# shield_draft.net
KiCad netlist of a schematic drawn in EAGLE
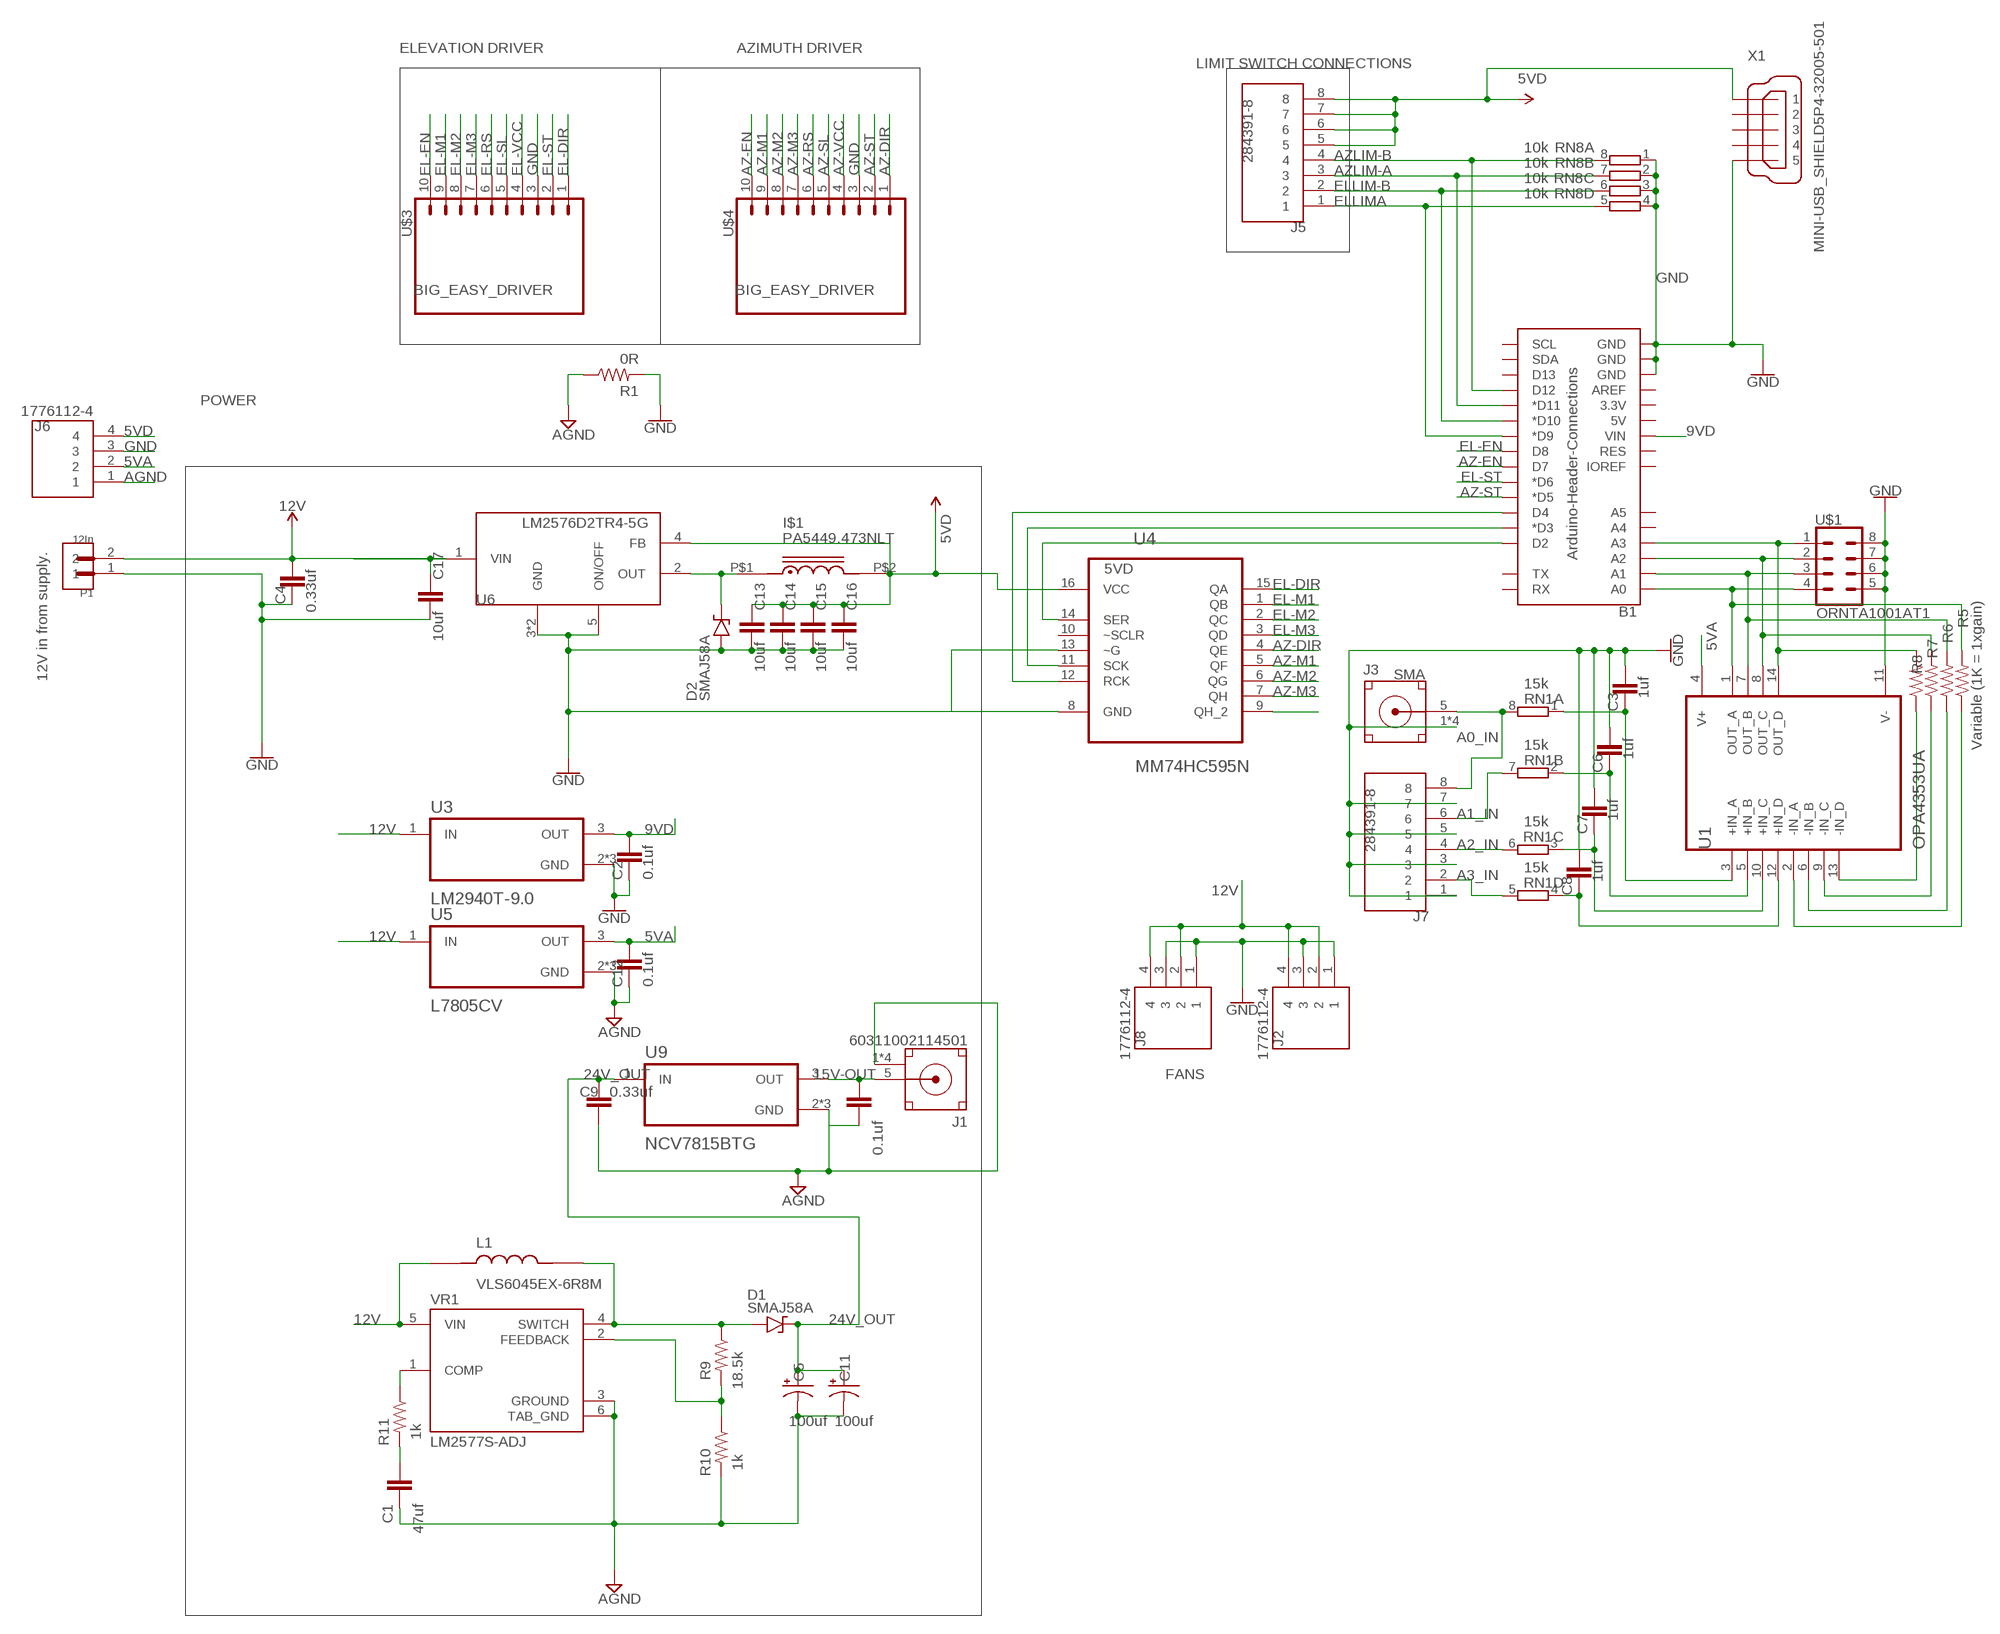
[diagram p0: schematic, sheet 1]

(export (version "E")
  (design (tool "Eeschema 10.0.6"))
  (components
    (comp (ref "B1")
      (value "Arduino-Header-Connections")
      (footprint "eagle-import:UNO_R3_SHIELD")
      (libsource (lib "eagle-import") (part "ARDUINO_UNO_R3_SHIELDBASIC"))
    )
    (comp (ref "C1")
      (value "47uf")
      (footprint "eagle-import:CAP_0805")
      (fields
        (field (name "DIGIKEY_PART_NUMBER") "311-1140-2-ND")
        (field (name "MANUFACTURER") "Yageo")
        (field (name "MPN") "CC0805KRX7R9BB104")
        (field (name "CREATED_BY") "PCBLayout.com")
      )
      (libsource (lib "eagle-import") (part "CC0805KRX7R9BB104"))
    )
    (comp (ref "C2")
      (value "0.1uf")
      (footprint "eagle-import:CAP_0805")
      (fields
        (field (name "DIGIKEY_PART_NUMBER") "311-1140-2-ND")
        (field (name "MANUFACTURER") "Yageo")
        (field (name "MPN") "CC0805KRX7R9BB104")
        (field (name "CREATED_BY") "PCBLayout.com")
      )
      (libsource (lib "eagle-import") (part "CC0805KRX7R9BB104"))
    )
    (comp (ref "C3")
      (value "1uf")
      (footprint "eagle-import:CAP_0805")
      (fields
        (field (name "DIGIKEY_PART_NUMBER") "311-1140-2-ND")
        (field (name "MANUFACTURER") "Yageo")
        (field (name "MPN") "CC0805KRX7R9BB104")
        (field (name "CREATED_BY") "PCBLayout.com")
      )
      (libsource (lib "eagle-import") (part "CC0805KRX7R9BB104"))
    )
    (comp (ref "C4")
      (value "0.33uf")
      (footprint "eagle-import:CAP_0805")
      (fields
        (field (name "DIGIKEY_PART_NUMBER") "311-1140-2-ND")
        (field (name "MANUFACTURER") "Yageo")
        (field (name "MPN") "CC0805KRX7R9BB104")
        (field (name "CREATED_BY") "PCBLayout.com")
      )
      (libsource (lib "eagle-import") (part "CC0805KRX7R9BB104"))
    )
    (comp (ref "C5")
      (value "100uf")
      (footprint "eagle-import:E5-10,5")
      (libsource (lib "eagle-import") (part "CAPACITOR-PE5-10.5"))
    )
    (comp (ref "C6")
      (value "1uf")
      (footprint "eagle-import:CAP_0805")
      (fields
        (field (name "DIGIKEY_PART_NUMBER") "311-1140-2-ND")
        (field (name "MANUFACTURER") "Yageo")
        (field (name "MPN") "CC0805KRX7R9BB104")
        (field (name "CREATED_BY") "PCBLayout.com")
      )
      (libsource (lib "eagle-import") (part "CC0805KRX7R9BB104"))
    )
    (comp (ref "C7")
      (value "1uf")
      (footprint "eagle-import:CAP_0805")
      (fields
        (field (name "DIGIKEY_PART_NUMBER") "311-1140-2-ND")
        (field (name "MANUFACTURER") "Yageo")
        (field (name "MPN") "CC0805KRX7R9BB104")
        (field (name "CREATED_BY") "PCBLayout.com")
      )
      (libsource (lib "eagle-import") (part "CC0805KRX7R9BB104"))
    )
    (comp (ref "C8")
      (value "1uf")
      (footprint "eagle-import:CAP_0805")
      (fields
        (field (name "DIGIKEY_PART_NUMBER") "311-1140-2-ND")
        (field (name "MANUFACTURER") "Yageo")
        (field (name "MPN") "CC0805KRX7R9BB104")
        (field (name "CREATED_BY") "PCBLayout.com")
      )
      (libsource (lib "eagle-import") (part "CC0805KRX7R9BB104"))
    )
    (comp (ref "C9")
      (value "0.33uf")
      (footprint "eagle-import:CAP_0805")
      (fields
        (field (name "DIGIKEY_PART_NUMBER") "311-1140-2-ND")
        (field (name "MANUFACTURER") "Yageo")
        (field (name "MPN") "CC0805KRX7R9BB104")
        (field (name "CREATED_BY") "PCBLayout.com")
      )
      (libsource (lib "eagle-import") (part "CC0805KRX7R9BB104"))
    )
    (comp (ref "C10")
      (value "0.1uf")
      (footprint "eagle-import:CAP_0805")
      (fields
        (field (name "DIGIKEY_PART_NUMBER") "311-1140-2-ND")
        (field (name "MANUFACTURER") "Yageo")
        (field (name "MPN") "CC0805KRX7R9BB104")
        (field (name "CREATED_BY") "PCBLayout.com")
      )
      (libsource (lib "eagle-import") (part "CC0805KRX7R9BB104"))
    )
    (comp (ref "C11")
      (value "100uf")
      (footprint "eagle-import:E5-10,5")
      (libsource (lib "eagle-import") (part "CAPACITOR-PE5-10.5"))
    )
    (comp (ref "C12")
      (value "0.1uf")
      (footprint "eagle-import:CAP_0805")
      (fields
        (field (name "DIGIKEY_PART_NUMBER") "311-1140-2-ND")
        (field (name "MANUFACTURER") "Yageo")
        (field (name "MPN") "CC0805KRX7R9BB104")
        (field (name "CREATED_BY") "PCBLayout.com")
      )
      (libsource (lib "eagle-import") (part "CC0805KRX7R9BB104"))
    )
    (comp (ref "C13")
      (value "10uf")
      (footprint "eagle-import:0805")
      (libsource (lib "eagle-import") (part "39NF-0805-50V-10%"))
    )
    (comp (ref "C14")
      (value "10uf")
      (footprint "eagle-import:0805")
      (libsource (lib "eagle-import") (part "39NF-0805-50V-10%"))
    )
    (comp (ref "C15")
      (value "10uf")
      (footprint "eagle-import:0805")
      (libsource (lib "eagle-import") (part "39NF-0805-50V-10%"))
    )
    (comp (ref "C16")
      (value "10uf")
      (footprint "eagle-import:0805")
      (libsource (lib "eagle-import") (part "39NF-0805-50V-10%"))
    )
    (comp (ref "C17")
      (value "10uf")
      (footprint "eagle-import:0805")
      (libsource (lib "eagle-import") (part "39NF-0805-50V-10%"))
    )
    (comp (ref "D1")
      (value "SMAJ58A")
      (footprint "eagle-import:SMA")
      (fields (field (name "MF") "Littelfuse Inc."))
      (libsource (lib "eagle-import") (part "SMAJ58A"))
    )
    (comp (ref "D2")
      (value "SMAJ58A")
      (footprint "eagle-import:SMA")
      (fields (field (name "MF") "Littelfuse Inc."))
      (libsource (lib "eagle-import") (part "SMAJ58A"))
    )
    (comp (ref "I$1")
      (value "PA5449.473NLT")
      (footprint "eagle-import:IND_TYS4020470M-10")
      (libsource (lib "eagle-import") (part "PULSE_ELECTRONICS_INDUCTOR"))
    )
    (comp (ref "J1")
      (value "60311002114501")
      (footprint "eagle-import:60311002114501")
      (fields
        (field (name "DIGIKEY_PART_NUMBER") "732-13833-ND")
        (field (name "MANUFACTURER") "Wurth Electronics Inc.")
        (field (name "CREATED_BY") "PCBLayout.com")
      )
      (libsource (lib "eagle-import") (part "60311002114501"))
    )
    (comp (ref "J2")
      (value "1776112-4")
      (footprint "eagle-import:TE_1776112-4")
      (fields (field (name "MF") "TE Connectivity"))
      (libsource (lib "eagle-import") (part "1776112-4"))
    )
    (comp (ref "J3")
      (value "SMA")
      (footprint "eagle-import:60311002114501")
      (fields
        (field (name "DIGIKEY_PART_NUMBER") "732-13833-ND")
        (field (name "MANUFACTURER") "Wurth Electronics Inc.")
        (field (name "MPN") "60311002114501")
        (field (name "CREATED_BY") "PCBLayout.com")
      )
      (libsource (lib "eagle-import") (part "60311002114501"))
    )
    (comp (ref "J5")
      (value "284391-8")
      (footprint "eagle-import:TE_284391-8")
      (fields (field (name "MF") "TE Connectivity"))
      (libsource (lib "eagle-import") (part "284391-8"))
    )
    (comp (ref "J6")
      (value "1776112-4")
      (footprint "eagle-import:TE_1776112-4")
      (fields (field (name "MF") "TE Connectivity"))
      (libsource (lib "eagle-import") (part "1776112-4"))
    )
    (comp (ref "J7")
      (value "284391-8")
      (footprint "eagle-import:TE_284391-8")
      (fields (field (name "MF") "TE Connectivity"))
      (libsource (lib "eagle-import") (part "284391-8"))
    )
    (comp (ref "J8")
      (value "1776112-4")
      (footprint "eagle-import:TE_1776112-4")
      (fields (field (name "MF") "TE Connectivity"))
      (libsource (lib "eagle-import") (part "1776112-4"))
    )
    (comp (ref "L1")
      (value "VLS6045EX-6R8M")
      (footprint "eagle-import:IND_VLS6045EX-6R8M")
      (fields (field (name "MF") "TDK") (field (name "MP") "VLS6045EX6R8M"))
      (libsource (lib "eagle-import") (part "VLS6045EX-6R8M"))
    )
    (comp (ref "P1")
      (value "12In")
      (footprint "eagle-import:OST_OSTTE020104")
      (fields (field (name "MF") "On Shore") (field (name "MP") "OSTTE020104"))
      (libsource (lib "eagle-import") (part "OSTTE020104"))
    )
    (comp (ref "R1")
      (value "0R")
      (footprint "eagle-import:0603")
      (libsource (lib "eagle-import") (part "1OHM-0603-1/10W-1%"))
    )
    (comp (ref "R5")
      (value "Variable (1K = 1xgain)")
      (footprint "eagle-import:RESAD1176W63L850D250B")
      (libsource (lib "eagle-import") (part "R-USAXIAL-11.7MM-PITCH_"))
    )
    (comp (ref "R6")
      (value "Var")
      (footprint "eagle-import:RESAD1176W63L850D250B")
      (libsource (lib "eagle-import") (part "R-USAXIAL-11.7MM-PITCH_"))
    )
    (comp (ref "R7")
      (value "Var")
      (footprint "eagle-import:RESAD1176W63L850D250B")
      (libsource (lib "eagle-import") (part "R-USAXIAL-11.7MM-PITCH_"))
    )
    (comp (ref "R8")
      (value "Var")
      (footprint "eagle-import:RESAD1176W63L850D250B")
      (libsource (lib "eagle-import") (part "R-USAXIAL-11.7MM-PITCH_"))
    )
    (comp (ref "R9")
      (value "18.5k")
      (footprint "eagle-import:0603")
      (libsource (lib "eagle-import") (part "1OHM-0603-1/10W-1%"))
    )
    (comp (ref "R10")
      (value "1k")
      (footprint "eagle-import:0603")
      (libsource (lib "eagle-import") (part "1OHM-0603-1/10W-1%"))
    )
    (comp (ref "R11")
      (value "1k")
      (footprint "eagle-import:0603")
      (libsource (lib "eagle-import") (part "1OHM-0603-1/10W-1%"))
    )
    (comp (ref "RN1")
      (value "15k")
      (footprint "eagle-import:CAY16")
      (fields (field (name "PART_NUMBER") "064R_10K_/_CAY16-103J4LF"))
      (libsource (lib "eagle-import") (part "0016_064R_10K_/_CAY16-103J4LF"))
    )
    (comp (ref "RN8")
      (value "10k")
      (footprint "eagle-import:CAY16")
      (fields (field (name "PART_NUMBER") "064R_10K_/_CAY16-103J4LF"))
      (libsource (lib "eagle-import") (part "0016_064R_10K_/_CAY16-103J4LF"))
    )
    (comp (ref "U$1")
      (value "ORNTA1001AT1")
      (footprint "eagle-import:SOIC127P600X175-8N")
      (libsource (lib "eagle-import") (part "ORNTA1001AT1"))
    )
    (comp (ref "U$3")
      (value "BIG_EASY_DRIVER")
      (footprint "eagle-import:EASY_DRIVER_FTPRT")
      (libsource (lib "eagle-import") (part "BIG_EASY_DRIVER"))
    )
    (comp (ref "U$4")
      (value "BIG_EASY_DRIVER")
      (footprint "eagle-import:EASY_DRIVER_FTPRT")
      (libsource (lib "eagle-import") (part "BIG_EASY_DRIVER"))
    )
    (comp (ref "U1")
      (value "OPA4353UA")
      (footprint "eagle-import:SOIC127P600X175-14N")
      (fields (field (name "MF") "Texas Instruments"))
      (libsource (lib "eagle-import") (part "OPA4353UA"))
    )
    (comp (ref "U3")
      (value "LM2940T-9.0")
      (footprint "eagle-import:TO254P1054X470X1955-3")
      (fields (field (name "MF") "Texas Instruments") (field (name "MP") "LM2940T-9.0/NOPB"))
      (libsource (lib "eagle-import") (part "LM2940T-9.0"))
    )
    (comp (ref "U4")
      (value "MM74HC595N")
      (footprint "eagle-import:DIP254P762X533-16")
      (fields (field (name "MF") "ON Semiconductor"))
      (libsource (lib "eagle-import") (part "MM74HC595N"))
    )
    (comp (ref "U5")
      (value "L7805CV")
      (footprint "eagle-import:TO254P1054X470X1955-3")
      (fields (field (name "MF") "Texas Instruments") (field (name "MP") "LM2940T-9.0/NOPB"))
      (libsource (lib "eagle-import") (part "LM2940T-9.0"))
    )
    (comp (ref "U6")
      (value "LM2576D2TR4-5G")
      (footprint "eagle-import:D2PAK-5")
      (fields (field (name "MF") "ON Semiconductor"))
      (libsource (lib "eagle-import") (part "LM2576D2TR4-5G"))
    )
    (comp (ref "U9")
      (value "NCV7815BTG")
      (footprint "eagle-import:TO254P1054X470X1955-3")
      (fields (field (name "MF") "Texas Instruments") (field (name "MP") "LM2940T-9.0/NOPB"))
      (libsource (lib "eagle-import") (part "LM2940T-9.0"))
    )
    (comp (ref "VR1")
      (value "LM2577S-ADJ")
      (footprint "eagle-import:TO170P1524X483-6N")
      (fields (field (name "MF") "Texas Instruments"))
      (libsource (lib "eagle-import") (part "LM2577S-ADJ"))
    )
    (comp (ref "X1")
      (value "MINI-USB_SHIELD5P4-32005-501")
      (footprint "eagle-import:32005-501")
      (libsource (lib "eagle-import") (part "MINI-USB_SHIELD5P4-32005-501"))
    )
  )
  (nets
    (net (code "1") (name "/5VA") (class "Default")
      (node (ref "C12") (pin "2") (pinfunction "2_2") (pintype "passive"))
      (node (ref "J6") (pin "2") (pinfunction "2_2") (pintype "passive"))
      (node (ref "U1") (pin "4") (pinfunction "V+_4") (pintype "power_in"))
      (node (ref "U5") (pin "3") (pinfunction "OUT_3") (pintype "output"))
    )
    (net (code "2") (name "/9VD") (class "Default")
      (node (ref "B1") (pin "VIN") (pinfunction "VIN_VIN") (pintype "bidirectional"))
      (node (ref "C2") (pin "2") (pinfunction "2_2") (pintype "passive"))
      (node (ref "U3") (pin "3") (pinfunction "OUT_3") (pintype "output"))
    )
    (net (code "3") (name "/15V-OUT") (class "Default")
      (node (ref "C10") (pin "2") (pinfunction "2_2") (pintype "passive"))
      (node (ref "J1") (pin "5") (pinfunction "SIGNAL_5") (pintype "passive"))
      (node (ref "U9") (pin "3") (pinfunction "OUT_3") (pintype "output"))
    )
    (net (code "4") (name "/24V_OUT") (class "Default")
      (node (ref "C11") (pin "+") (pinfunction "+_+") (pintype "passive"))
      (node (ref "C5") (pin "+") (pinfunction "+_+") (pintype "passive"))
      (node (ref "C9") (pin "2") (pinfunction "2_2") (pintype "passive"))
      (node (ref "D1") (pin "C") (pinfunction "C_C") (pintype "passive"))
      (node (ref "U9") (pin "1") (pinfunction "IN_1") (pintype "input"))
    )
    (net (code "5") (name "/A0_IN") (class "Default")
      (node (ref "J3") (pin "5") (pinfunction "SIGNAL_5") (pintype "passive"))
      (node (ref "J7") (pin "8") (pinfunction "8_8") (pintype "passive"))
      (node (ref "RN1") (pin "8") (pinfunction "2_8") (pintype "passive"))
    )
    (net (code "6") (name "/A1_IN") (class "Default")
      (node (ref "J7") (pin "6") (pinfunction "6_6") (pintype "passive"))
      (node (ref "RN1") (pin "7") (pinfunction "2_7") (pintype "passive"))
    )
    (net (code "7") (name "/A2_IN") (class "Default")
      (node (ref "J7") (pin "4") (pinfunction "4_4") (pintype "passive"))
      (node (ref "RN1") (pin "6") (pinfunction "2_6") (pintype "passive"))
    )
    (net (code "8") (name "/A3_IN") (class "Default")
      (node (ref "J7") (pin "2") (pinfunction "2_2") (pintype "passive"))
      (node (ref "RN1") (pin "5") (pinfunction "2_5") (pintype "passive"))
    )
    (net (code "9") (name "/AZ-DIR") (class "Default")
      (node (ref "U$4") (pin "1") (pinfunction "1_1") (pintype "passive"))
      (node (ref "U4") (pin "4") (pinfunction "QE_4") (pintype "output"))
    )
    (net (code "10") (name "/AZ-EN") (class "Default")
      (node (ref "B1") (pin "D7") (pinfunction "D7_D7") (pintype "bidirectional"))
      (node (ref "U$4") (pin "10") (pinfunction "10_10") (pintype "passive"))
    )
    (net (code "11") (name "/AZ-M1") (class "Default")
      (node (ref "U$4") (pin "9") (pinfunction "9_9") (pintype "passive"))
      (node (ref "U4") (pin "5") (pinfunction "QF_5") (pintype "output"))
    )
    (net (code "12") (name "/AZ-M2") (class "Default")
      (node (ref "U$4") (pin "8") (pinfunction "8_8") (pintype "passive"))
      (node (ref "U4") (pin "6") (pinfunction "QG_6") (pintype "output"))
    )
    (net (code "13") (name "/AZ-M3") (class "Default")
      (node (ref "U$4") (pin "7") (pinfunction "7_7") (pintype "passive"))
      (node (ref "U4") (pin "7") (pinfunction "QH_7") (pintype "output"))
    )
    (net (code "14") (name "/AZ-RS") (class "Default")
      (node (ref "U$4") (pin "6") (pinfunction "6_6") (pintype "passive"))
    )
    (net (code "15") (name "/AZ-SL") (class "Default")
      (node (ref "U$4") (pin "5") (pinfunction "5_5") (pintype "passive"))
    )
    (net (code "16") (name "/AZ-ST") (class "Default")
      (node (ref "B1") (pin "D5") (pinfunction "*D5_D5") (pintype "bidirectional"))
      (node (ref "U$4") (pin "2") (pinfunction "2_2") (pintype "passive"))
    )
    (net (code "17") (name "/AZ-VCC") (class "Default")
      (node (ref "U$4") (pin "4") (pinfunction "4_4") (pintype "passive"))
    )
    (net (code "18") (name "/AZLIM-A") (class "Default")
      (node (ref "B1") (pin "D11") (pinfunction "*D11_D11") (pintype "bidirectional"))
      (node (ref "J5") (pin "3") (pinfunction "3_3") (pintype "passive"))
      (node (ref "RN8") (pin "7") (pinfunction "2_7") (pintype "passive"))
    )
    (net (code "19") (name "/AZLIM-B") (class "Default")
      (node (ref "B1") (pin "D12") (pinfunction "D12_D12") (pintype "bidirectional"))
      (node (ref "J5") (pin "4") (pinfunction "4_4") (pintype "passive"))
      (node (ref "RN8") (pin "8") (pinfunction "2_8") (pintype "passive"))
    )
    (net (code "20") (name "/EL-DIR") (class "Default")
      (node (ref "U$3") (pin "1") (pinfunction "1_1") (pintype "passive"))
      (node (ref "U4") (pin "15") (pinfunction "QA_15") (pintype "output"))
    )
    (net (code "21") (name "/EL-EN") (class "Default")
      (node (ref "B1") (pin "D8") (pinfunction "D8_D8") (pintype "bidirectional"))
      (node (ref "U$3") (pin "10") (pinfunction "10_10") (pintype "passive"))
    )
    (net (code "22") (name "/EL-M1") (class "Default")
      (node (ref "U$3") (pin "9") (pinfunction "9_9") (pintype "passive"))
      (node (ref "U4") (pin "1") (pinfunction "QB_1") (pintype "output"))
    )
    (net (code "23") (name "/EL-M2") (class "Default")
      (node (ref "U$3") (pin "8") (pinfunction "8_8") (pintype "passive"))
      (node (ref "U4") (pin "2") (pinfunction "QC_2") (pintype "output"))
    )
    (net (code "24") (name "/EL-M3") (class "Default")
      (node (ref "U$3") (pin "7") (pinfunction "7_7") (pintype "passive"))
      (node (ref "U4") (pin "3") (pinfunction "QD_3") (pintype "output"))
    )
    (net (code "25") (name "/EL-RS") (class "Default")
      (node (ref "U$3") (pin "6") (pinfunction "6_6") (pintype "passive"))
    )
    (net (code "26") (name "/EL-SL") (class "Default")
      (node (ref "U$3") (pin "5") (pinfunction "5_5") (pintype "passive"))
    )
    (net (code "27") (name "/EL-ST") (class "Default")
      (node (ref "B1") (pin "D6") (pinfunction "*D6_D6") (pintype "bidirectional"))
      (node (ref "U$3") (pin "2") (pinfunction "2_2") (pintype "passive"))
    )
    (net (code "28") (name "/EL-VCC") (class "Default")
      (node (ref "U$3") (pin "4") (pinfunction "4_4") (pintype "passive"))
    )
    (net (code "29") (name "/ELLIM-B") (class "Default")
      (node (ref "B1") (pin "D10") (pinfunction "*D10_D10") (pintype "bidirectional"))
      (node (ref "J5") (pin "2") (pinfunction "2_2") (pintype "passive"))
      (node (ref "RN8") (pin "6") (pinfunction "2_6") (pintype "passive"))
    )
    (net (code "30") (name "/ELLIMA") (class "Default")
      (node (ref "B1") (pin "D9") (pinfunction "*D9_D9") (pintype "bidirectional"))
      (node (ref "J5") (pin "1") (pinfunction "1_1") (pintype "passive"))
      (node (ref "RN8") (pin "5") (pinfunction "2_5") (pintype "passive"))
    )
    (net (code "31") (name "5V") (class "Default")
      (node (ref "C13") (pin "1") (pinfunction "1_1") (pintype "passive"))
      (node (ref "C14") (pin "1") (pinfunction "1_1") (pintype "passive"))
      (node (ref "C15") (pin "1") (pinfunction "1_1") (pintype "passive"))
      (node (ref "C16") (pin "1") (pinfunction "1_1") (pintype "passive"))
      (node (ref "I$1") (pin "P$2") (pinfunction "2_P$2") (pintype "passive"))
      (node (ref "J5") (pin "5") (pinfunction "5_5") (pintype "passive"))
      (node (ref "J5") (pin "6") (pinfunction "6_6") (pintype "passive"))
      (node (ref "J5") (pin "7") (pinfunction "7_7") (pintype "passive"))
      (node (ref "J5") (pin "8") (pinfunction "8_8") (pintype "passive"))
      (node (ref "J6") (pin "4") (pinfunction "4_4") (pintype "passive"))
      (node (ref "U4") (pin "16") (pinfunction "VCC_16") (pintype "power_in"))
      (node (ref "U6") (pin "4") (pinfunction "FB_4") (pintype "output"))
      (node (ref "X1") (pin "1") (pinfunction "1_1") (pintype "passive"))
    )
    (net (code "32") (name "12V") (class "Default")
      (node (ref "C17") (pin "1") (pinfunction "1_1") (pintype "passive"))
      (node (ref "C4") (pin "2") (pinfunction "2_2") (pintype "passive"))
      (node (ref "J2") (pin "2") (pinfunction "2_2") (pintype "passive"))
      (node (ref "J2") (pin "4") (pinfunction "4_4") (pintype "passive"))
      (node (ref "J8") (pin "2") (pinfunction "2_2") (pintype "passive"))
      (node (ref "J8") (pin "4") (pinfunction "4_4") (pintype "passive"))
      (node (ref "L1") (pin "1") (pinfunction "1_1") (pintype "passive"))
      (node (ref "P1") (pin "2") (pinfunction "2_2") (pintype "passive"))
      (node (ref "U3") (pin "1") (pinfunction "IN_1") (pintype "input"))
      (node (ref "U5") (pin "1") (pinfunction "IN_1") (pintype "input"))
      (node (ref "U6") (pin "1") (pinfunction "VIN_1") (pintype "input"))
      (node (ref "VR1") (pin "5") (pinfunction "VIN_5") (pintype "input"))
    )
    (net (code "33") (name "AGND") (class "Default")
      (node (ref "C1") (pin "1") (pinfunction "1_1") (pintype "passive"))
      (node (ref "C10") (pin "1") (pinfunction "1_1") (pintype "passive"))
      (node (ref "C11") (pin "-") (pinfunction "-_-") (pintype "passive"))
      (node (ref "C12") (pin "1") (pinfunction "1_1") (pintype "passive"))
      (node (ref "C5") (pin "-") (pinfunction "-_-") (pintype "passive"))
      (node (ref "C9") (pin "1") (pinfunction "1_1") (pintype "passive"))
      (node (ref "J1") (pin "1") (pinfunction "GND_1") (pintype "power_in"))
      (node (ref "J1") (pin "2") (pinfunction "GND_2") (pintype "power_in"))
      (node (ref "J1") (pin "3") (pinfunction "GND_3") (pintype "power_in"))
      (node (ref "J1") (pin "4") (pinfunction "GND_4") (pintype "power_in"))
      (node (ref "J6") (pin "1") (pinfunction "1_1") (pintype "passive"))
      (node (ref "R1") (pin "1") (pinfunction "1_1") (pintype "passive"))
      (node (ref "R10") (pin "2") (pinfunction "2_2") (pintype "passive"))
      (node (ref "U5") (pin "2") (pinfunction "GND_2") (pintype "power_in"))
      (node (ref "U5") (pin "P$1") (pinfunction "GND_P$1") (pintype "power_in"))
      (node (ref "U5") (pin "P$2") (pinfunction "GND_P$2") (pintype "power_in"))
      (node (ref "U9") (pin "2") (pinfunction "GND_2") (pintype "power_in"))
      (node (ref "U9") (pin "P$1") (pinfunction "GND_P$1") (pintype "power_in"))
      (node (ref "U9") (pin "P$2") (pinfunction "GND_P$2") (pintype "power_in"))
      (node (ref "VR1") (pin "3") (pinfunction "GROUND_3") (pintype "power_in"))
      (node (ref "VR1") (pin "6") (pinfunction "TAB_GND_6") (pintype "power_in"))
    )
    (net (code "34") (name "GND") (class "Default")
      (node (ref "B1") (pin "GND@0") (pinfunction "GND_GND@0") (pintype "bidirectional"))
      (node (ref "B1") (pin "GND@1") (pinfunction "GND_GND@1") (pintype "bidirectional"))
      (node (ref "B1") (pin "GND@2") (pinfunction "GND_GND@2") (pintype "bidirectional"))
      (node (ref "C13") (pin "2") (pinfunction "2_2") (pintype "passive"))
      (node (ref "C14") (pin "2") (pinfunction "2_2") (pintype "passive"))
      (node (ref "C15") (pin "2") (pinfunction "2_2") (pintype "passive"))
      (node (ref "C16") (pin "2") (pinfunction "2_2") (pintype "passive"))
      (node (ref "C17") (pin "2") (pinfunction "2_2") (pintype "passive"))
      (node (ref "C2") (pin "1") (pinfunction "1_1") (pintype "passive"))
      (node (ref "C3") (pin "2") (pinfunction "2_2") (pintype "passive"))
      (node (ref "C4") (pin "1") (pinfunction "1_1") (pintype "passive"))
      (node (ref "C6") (pin "2") (pinfunction "2_2") (pintype "passive"))
      (node (ref "C7") (pin "2") (pinfunction "2_2") (pintype "passive"))
      (node (ref "C8") (pin "2") (pinfunction "2_2") (pintype "passive"))
      (node (ref "D2") (pin "A") (pinfunction "A_A") (pintype "passive"))
      (node (ref "J2") (pin "1") (pinfunction "1_1") (pintype "passive"))
      (node (ref "J2") (pin "3") (pinfunction "3_3") (pintype "passive"))
      (node (ref "J3") (pin "1") (pinfunction "GND_1") (pintype "power_in"))
      (node (ref "J3") (pin "2") (pinfunction "GND_2") (pintype "power_in"))
      (node (ref "J3") (pin "3") (pinfunction "GND_3") (pintype "power_in"))
      (node (ref "J3") (pin "4") (pinfunction "GND_4") (pintype "power_in"))
      (node (ref "J6") (pin "3") (pinfunction "3_3") (pintype "passive"))
      (node (ref "J7") (pin "1") (pinfunction "1_1") (pintype "passive"))
      (node (ref "J7") (pin "3") (pinfunction "3_3") (pintype "passive"))
      (node (ref "J7") (pin "5") (pinfunction "5_5") (pintype "passive"))
      (node (ref "J7") (pin "7") (pinfunction "7_7") (pintype "passive"))
      (node (ref "J8") (pin "1") (pinfunction "1_1") (pintype "passive"))
      (node (ref "J8") (pin "3") (pinfunction "3_3") (pintype "passive"))
      (node (ref "P1") (pin "1") (pinfunction "1_1") (pintype "passive"))
      (node (ref "R1") (pin "2") (pinfunction "2_2") (pintype "passive"))
      (node (ref "RN8") (pin "1") (pinfunction "1_1") (pintype "passive"))
      (node (ref "RN8") (pin "2") (pinfunction "1_2") (pintype "passive"))
      (node (ref "RN8") (pin "3") (pinfunction "1_3") (pintype "passive"))
      (node (ref "RN8") (pin "4") (pinfunction "1_4") (pintype "passive"))
      (node (ref "U$1") (pin "5") (pinfunction "R4B_5") (pintype "passive"))
      (node (ref "U$1") (pin "6") (pinfunction "R3B_6") (pintype "passive"))
      (node (ref "U$1") (pin "7") (pinfunction "R2B_7") (pintype "passive"))
      (node (ref "U$1") (pin "8") (pinfunction "R1B_8") (pintype "passive"))
      (node (ref "U$3") (pin "3") (pinfunction "3_3") (pintype "passive"))
      (node (ref "U$4") (pin "3") (pinfunction "3_3") (pintype "passive"))
      (node (ref "U1") (pin "11") (pinfunction "V-_11") (pintype "power_in"))
      (node (ref "U3") (pin "2") (pinfunction "GND_2") (pintype "power_in"))
      (node (ref "U3") (pin "P$1") (pinfunction "GND_P$1") (pintype "power_in"))
      (node (ref "U3") (pin "P$2") (pinfunction "GND_P$2") (pintype "power_in"))
      (node (ref "U4") (pin "13") (pinfunction "~{G}_13") (pintype "input"))
      (node (ref "U4") (pin "8") (pinfunction "GND_8") (pintype "passive"))
      (node (ref "U6") (pin "3") (pinfunction "GND_3") (pintype "passive"))
      (node (ref "U6") (pin "5") (pinfunction "ON/OFF_5") (pintype "input"))
      (node (ref "U6") (pin "6") (pinfunction "GND_6") (pintype "passive"))
      (node (ref "X1") (pin "5") (pinfunction "5_5") (pintype "passive"))
    )
    (net (code "35") (name "Net-(B1-*D3)") (class "Default")
      (node (ref "B1") (pin "D3") (pinfunction "*D3_D3") (pintype "bidirectional"))
      (node (ref "U4") (pin "11") (pinfunction "SCK_11") (pintype "input"))
    )
    (net (code "36") (name "Net-(C1-Pad2)") (class "Default")
      (node (ref "C1") (pin "2") (pinfunction "2_2") (pintype "passive"))
      (node (ref "R11") (pin "2") (pinfunction "2_2") (pintype "passive"))
    )
    (net (code "37") (name "Net-(I$1-1)") (class "Default")
      (node (ref "D2") (pin "C") (pinfunction "C_C") (pintype "passive"))
      (node (ref "I$1") (pin "P$1") (pinfunction "1_P$1") (pintype "passive"))
      (node (ref "U6") (pin "2") (pinfunction "OUT_2") (pintype "output"))
    )
    (net (code "38") (name "Net-(RN1B-1)") (class "Default")
      (node (ref "C6") (pin "1") (pinfunction "1_1") (pintype "passive"))
      (node (ref "RN1") (pin "2") (pinfunction "1_2") (pintype "passive"))
      (node (ref "U1") (pin "5") (pinfunction "+IN_B_5") (pintype "input"))
    )
    (net (code "39") (name "Net-(RN1C-1)") (class "Default")
      (node (ref "C7") (pin "1") (pinfunction "1_1") (pintype "passive"))
      (node (ref "RN1") (pin "3") (pinfunction "1_3") (pintype "passive"))
      (node (ref "U1") (pin "10") (pinfunction "+IN_C_10") (pintype "input"))
    )
    (net (code "40") (name "Net-(RN1D-1)") (class "Default")
      (node (ref "C8") (pin "1") (pinfunction "1_1") (pintype "passive"))
      (node (ref "RN1") (pin "4") (pinfunction "1_4") (pintype "passive"))
      (node (ref "U1") (pin "12") (pinfunction "+IN_D_12") (pintype "input"))
    )
    (net (code "41") (name "Net-(U$1-R1A)") (class "Default")
      (node (ref "B1") (pin "A3") (pinfunction "A3_A3") (pintype "bidirectional"))
      (node (ref "R8") (pin "2") (pinfunction "2_2") (pintype "passive"))
      (node (ref "U$1") (pin "1") (pinfunction "R1A_1") (pintype "passive"))
      (node (ref "U1") (pin "14") (pinfunction "OUT_D_14") (pintype "output"))
    )
    (net (code "42") (name "Net-(U$1-R2A)") (class "Default")
      (node (ref "B1") (pin "A2") (pinfunction "A2_A2") (pintype "bidirectional"))
      (node (ref "R7") (pin "2") (pinfunction "2_2") (pintype "passive"))
      (node (ref "U$1") (pin "2") (pinfunction "R2A_2") (pintype "passive"))
      (node (ref "U1") (pin "8") (pinfunction "OUT_C_8") (pintype "output"))
    )
    (net (code "43") (name "Net-(U$1-R3A)") (class "Default")
      (node (ref "B1") (pin "A1") (pinfunction "A1_A1") (pintype "bidirectional"))
      (node (ref "R6") (pin "2") (pinfunction "2_2") (pintype "passive"))
      (node (ref "U$1") (pin "3") (pinfunction "R3A_3") (pintype "passive"))
      (node (ref "U1") (pin "7") (pinfunction "OUT_B_7") (pintype "output"))
    )
    (net (code "44") (name "Net-(U$1-R4A)") (class "Default")
      (node (ref "B1") (pin "A0") (pinfunction "A0_A0") (pintype "bidirectional"))
      (node (ref "R5") (pin "2") (pinfunction "2_2") (pintype "passive"))
      (node (ref "U$1") (pin "4") (pinfunction "R4A_4") (pintype "passive"))
      (node (ref "U1") (pin "1") (pinfunction "OUT_A_1") (pintype "output"))
    )
    (net (code "45") (name "Net-(U1-+IN_A)") (class "Default")
      (node (ref "C3") (pin "1") (pinfunction "1_1") (pintype "passive"))
      (node (ref "RN1") (pin "1") (pinfunction "1_1") (pintype "passive"))
      (node (ref "U1") (pin "3") (pinfunction "+IN_A_3") (pintype "input"))
    )
    (net (code "46") (name "Net-(U1--IN_A)") (class "Default")
      (node (ref "R5") (pin "1") (pinfunction "1_1") (pintype "passive"))
      (node (ref "U1") (pin "2") (pinfunction "-IN_A_2") (pintype "input"))
    )
    (net (code "47") (name "Net-(U1--IN_B)") (class "Default")
      (node (ref "R6") (pin "1") (pinfunction "1_1") (pintype "passive"))
      (node (ref "U1") (pin "6") (pinfunction "-IN_B_6") (pintype "input"))
    )
    (net (code "48") (name "Net-(U1--IN_C)") (class "Default")
      (node (ref "R7") (pin "1") (pinfunction "1_1") (pintype "passive"))
      (node (ref "U1") (pin "9") (pinfunction "-IN_C_9") (pintype "input"))
    )
    (net (code "49") (name "Net-(U1--IN_D)") (class "Default")
      (node (ref "R8") (pin "1") (pinfunction "1_1") (pintype "passive"))
      (node (ref "U1") (pin "13") (pinfunction "-IN_D_13") (pintype "input"))
    )
    (net (code "50") (name "Net-(U4-RCK)") (class "Default")
      (node (ref "B1") (pin "D4") (pinfunction "D4_D4") (pintype "bidirectional"))
      (node (ref "U4") (pin "12") (pinfunction "RCK_12") (pintype "input"))
    )
    (net (code "51") (name "Net-(U4-SER)") (class "Default")
      (node (ref "B1") (pin "D2") (pinfunction "D2_D2") (pintype "bidirectional"))
      (node (ref "U4") (pin "14") (pinfunction "SER_14") (pintype "input"))
    )
    (net (code "52") (name "Net-(VR1-COMP)") (class "Default")
      (node (ref "R11") (pin "1") (pinfunction "1_1") (pintype "passive"))
      (node (ref "VR1") (pin "1") (pinfunction "COMP_1") (pintype "passive"))
    )
    (net (code "53") (name "Net-(VR1-FEEDBACK)") (class "Default")
      (node (ref "R10") (pin "1") (pinfunction "1_1") (pintype "passive"))
      (node (ref "R9") (pin "2") (pinfunction "2_2") (pintype "passive"))
      (node (ref "VR1") (pin "2") (pinfunction "FEEDBACK_2") (pintype "input"))
    )
    (net (code "54") (name "Net-(VR1-SWITCH)") (class "Default")
      (node (ref "D1") (pin "A") (pinfunction "A_A") (pintype "passive"))
      (node (ref "L1") (pin "2") (pinfunction "2_2") (pintype "passive"))
      (node (ref "R9") (pin "1") (pinfunction "1_1") (pintype "passive"))
      (node (ref "VR1") (pin "4") (pinfunction "SWITCH_4") (pintype "output"))
    )
    (net (code "55") (name "unconnected-(B1-Pad3.3V)") (class "Default")
      (node (ref "B1") (pin "3.3V") (pinfunction "3.3V_3.3V") (pintype "bidirectional"))
    )
    (net (code "56") (name "unconnected-(B1-Pad5V)") (class "Default")
      (node (ref "B1") (pin "5V") (pinfunction "5V_5V") (pintype "bidirectional"))
    )
    (net (code "57") (name "unconnected-(B1-PadA4)") (class "Default")
      (node (ref "B1") (pin "A4") (pinfunction "A4_A4") (pintype "bidirectional"))
    )
    (net (code "58") (name "unconnected-(B1-PadA5)") (class "Default")
      (node (ref "B1") (pin "A5") (pinfunction "A5_A5") (pintype "bidirectional"))
    )
    (net (code "59") (name "unconnected-(B1-PadAREF)") (class "Default")
      (node (ref "B1") (pin "AREF") (pinfunction "AREF_AREF") (pintype "bidirectional"))
    )
    (net (code "60") (name "unconnected-(B1-PadD13)") (class "Default")
      (node (ref "B1") (pin "D13") (pinfunction "D13_D13") (pintype "bidirectional"))
    )
    (net (code "61") (name "unconnected-(B1-PadIOREF)") (class "Default")
      (node (ref "B1") (pin "IOREF") (pinfunction "IOREF_IOREF") (pintype "bidirectional"))
    )
    (net (code "62") (name "unconnected-(B1-PadRES)") (class "Default")
      (node (ref "B1") (pin "RES") (pinfunction "RES_RES") (pintype "bidirectional"))
    )
    (net (code "63") (name "unconnected-(B1-PadRX)") (class "Default")
      (node (ref "B1") (pin "RX") (pinfunction "RX_RX") (pintype "bidirectional"))
    )
    (net (code "64") (name "unconnected-(B1-PadSCL)") (class "Default")
      (node (ref "B1") (pin "SCL") (pinfunction "SCL_SCL") (pintype "bidirectional"))
    )
    (net (code "65") (name "unconnected-(B1-PadSDA)") (class "Default")
      (node (ref "B1") (pin "SDA") (pinfunction "SDA_SDA") (pintype "bidirectional"))
    )
    (net (code "66") (name "unconnected-(B1-PadTX)") (class "Default")
      (node (ref "B1") (pin "TX") (pinfunction "TX_TX") (pintype "bidirectional"))
    )
    (net (code "67") (name "unconnected-(U4-QH_2-Pad9)") (class "Default")
      (node (ref "U4") (pin "9") (pinfunction "QH_2_9") (pintype "output"))
    )
    (net (code "68") (name "unconnected-(U4-~{SCLR}-Pad10)") (class "Default")
      (node (ref "U4") (pin "10") (pinfunction "~{SCLR}_10") (pintype "input"))
    )
    (net (code "69") (name "unconnected-(X1-Pad2)") (class "Default")
      (node (ref "X1") (pin "2") (pinfunction "2_2") (pintype "passive"))
    )
    (net (code "70") (name "unconnected-(X1-Pad3)") (class "Default")
      (node (ref "X1") (pin "3") (pinfunction "3_3") (pintype "passive"))
    )
    (net (code "71") (name "unconnected-(X1-Pad4)") (class "Default")
      (node (ref "X1") (pin "4") (pinfunction "4_4") (pintype "passive"))
    )
  )
)
